# HV_amplifier.net
KiCad netlist of a schematic drawn in Altium Designer
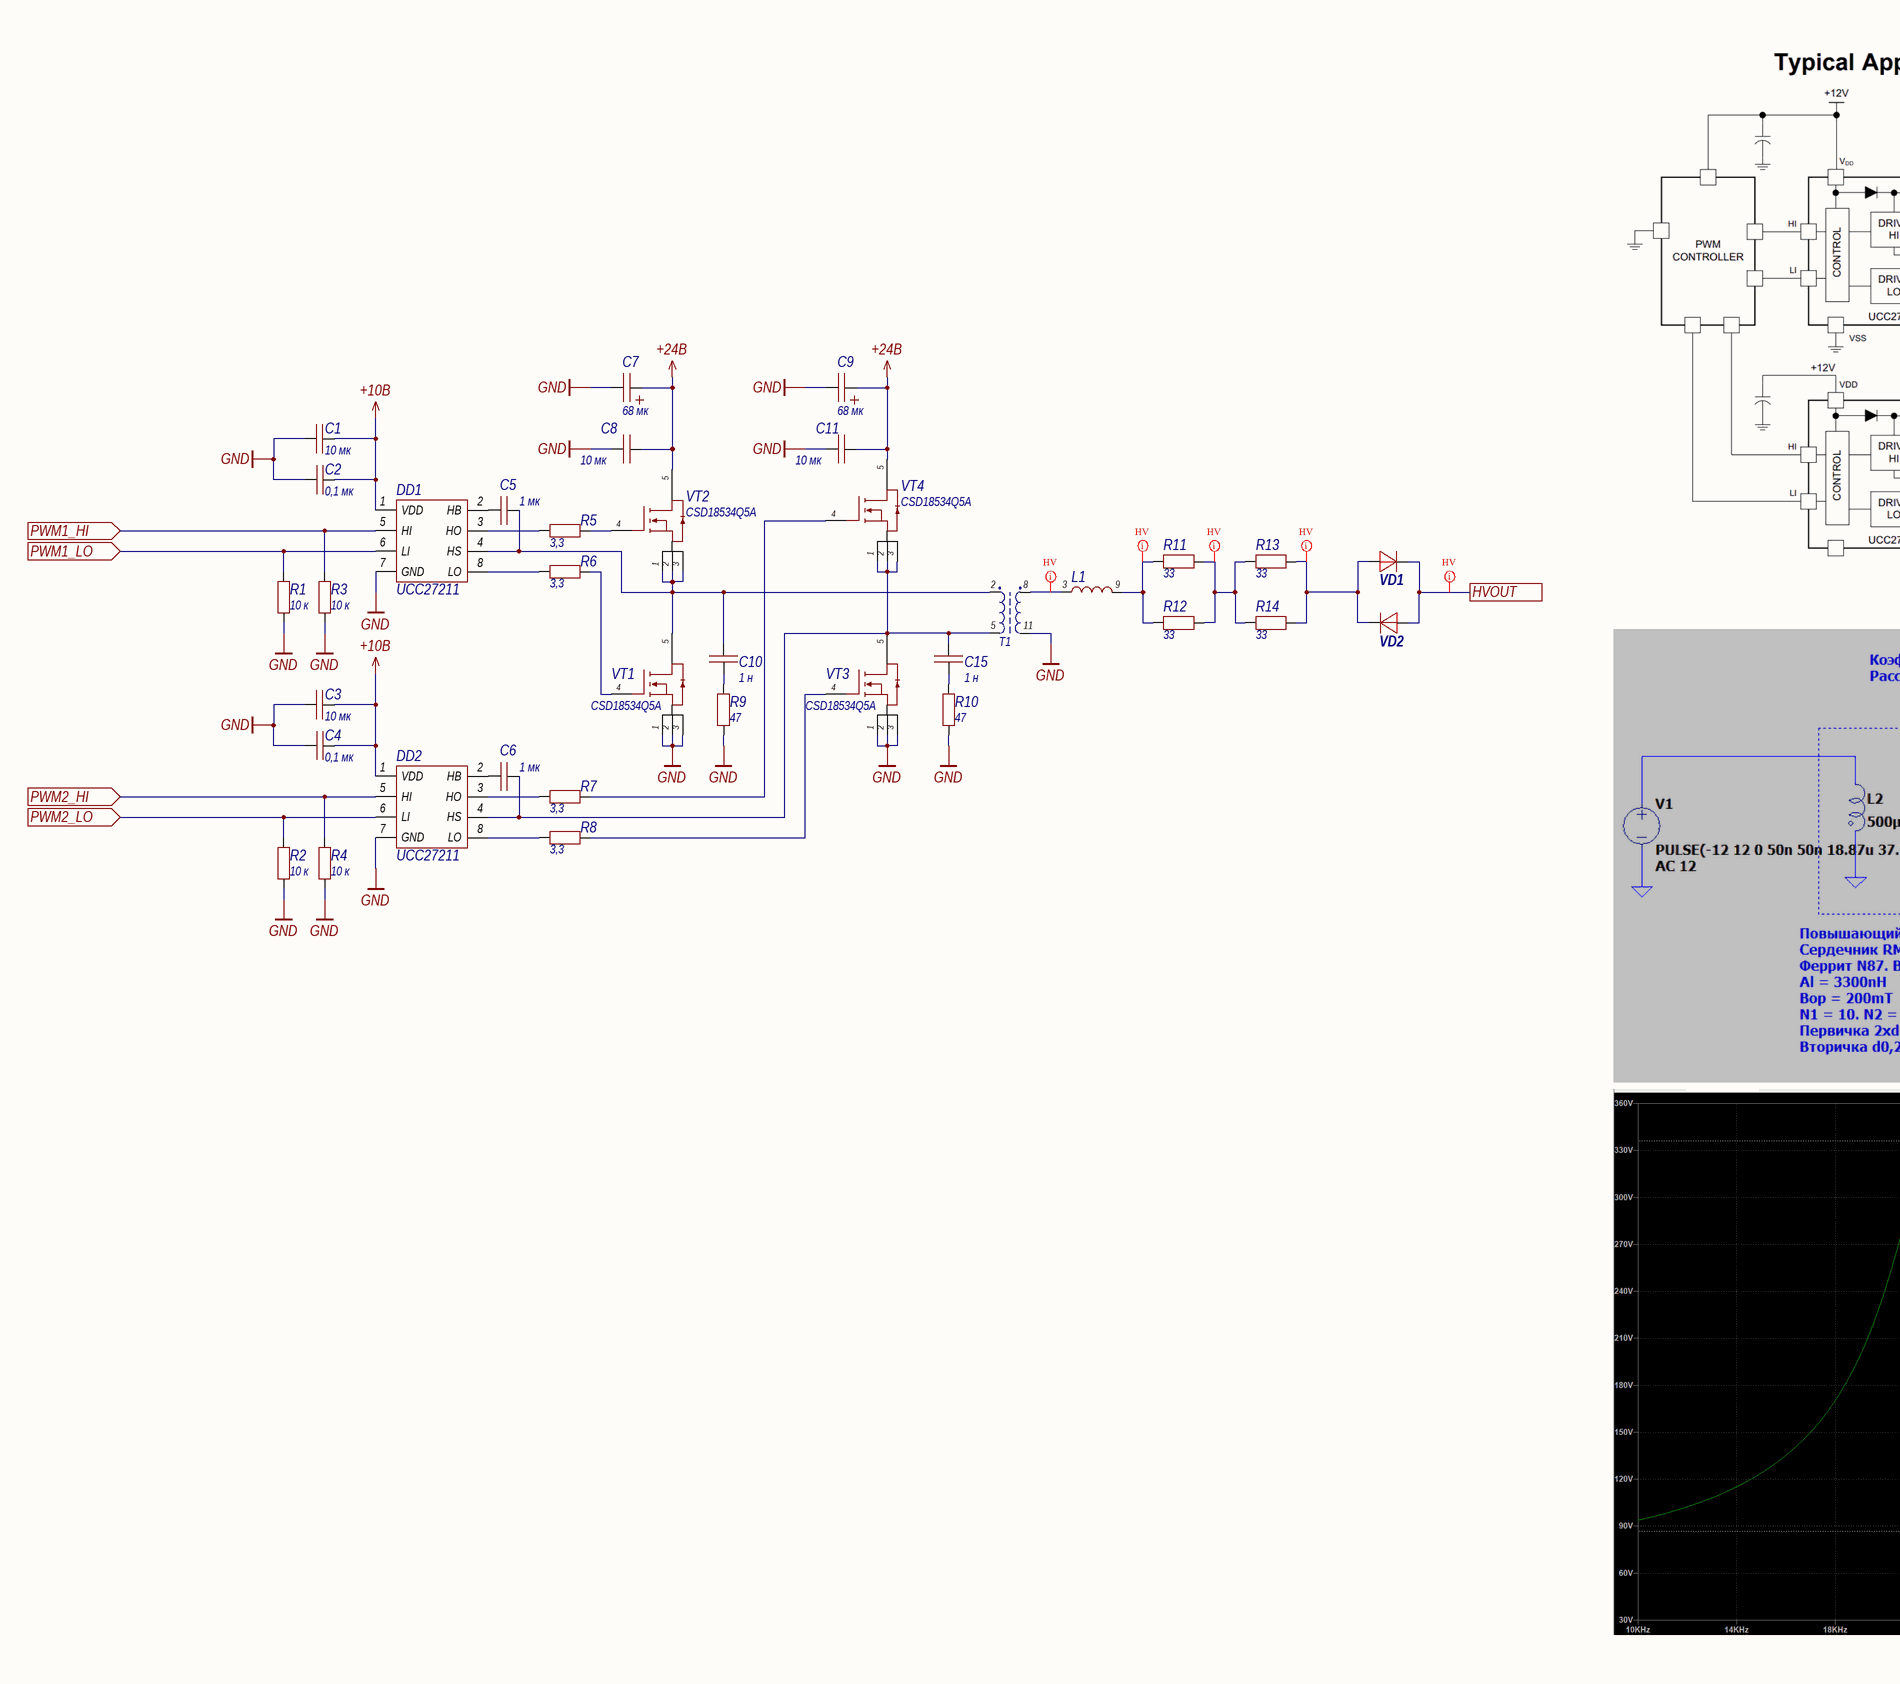
[diagram p0: HV_amplifier.SchDoc, left]
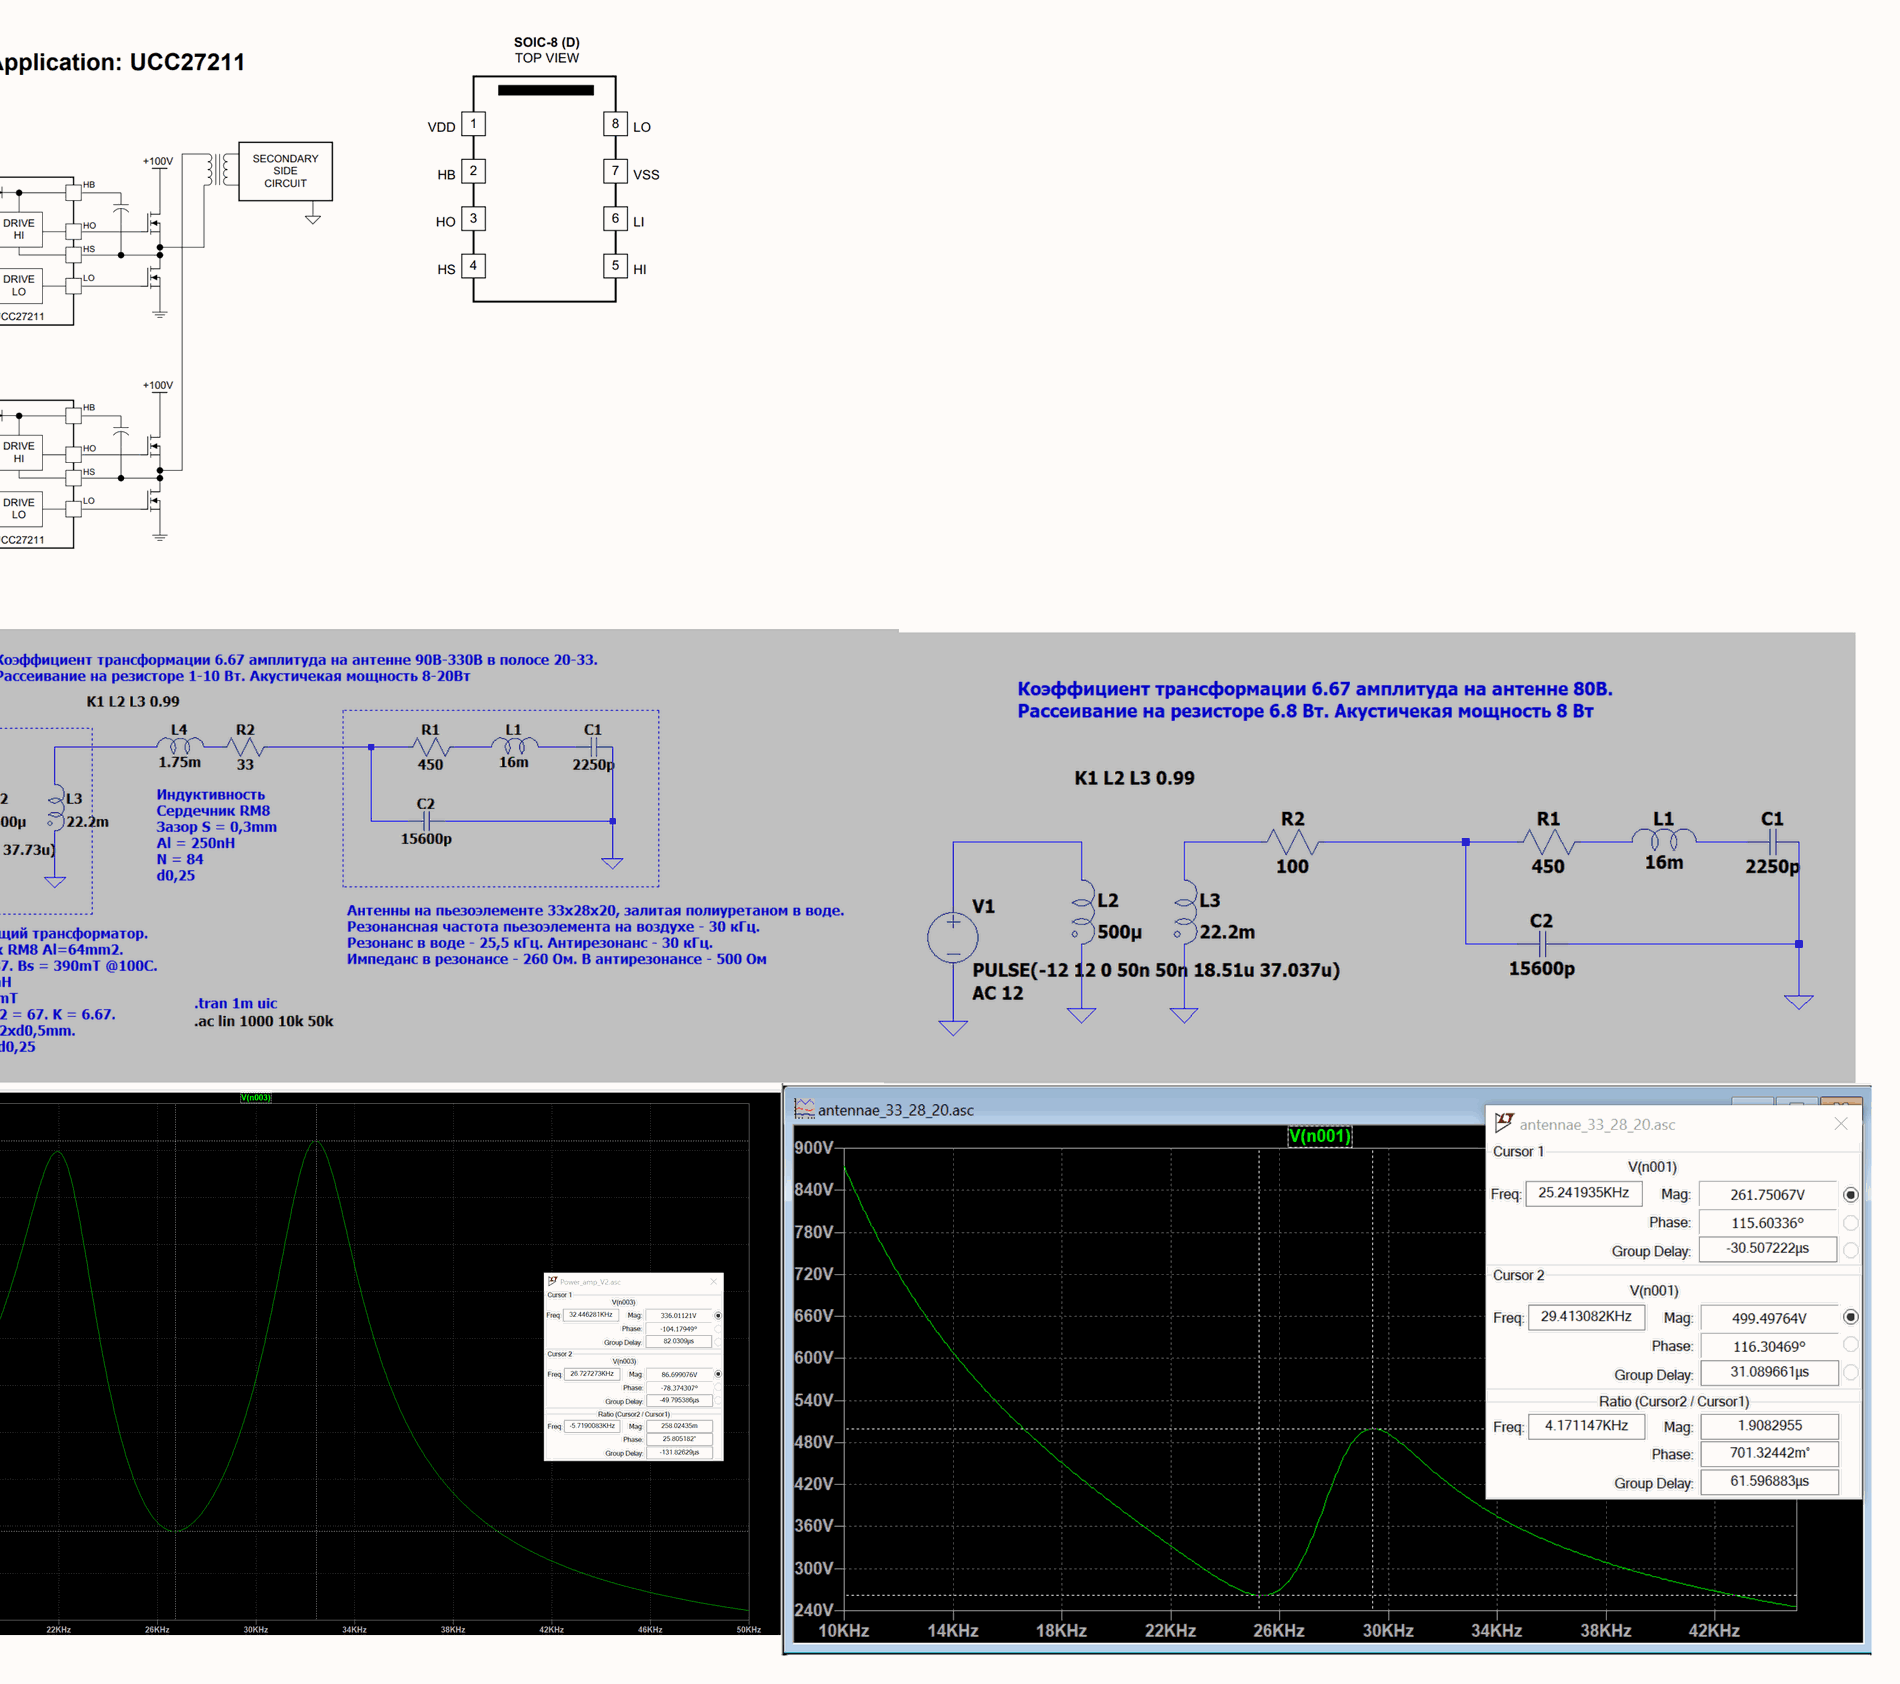
[diagram p1: HV_amplifier.SchDoc, right]

(export (version "E")
  (design (tool "Eeschema 10.0.6"))
  (components
    (comp (ref "C1")
      (value "10 мк")
      (footprint "1210C")
      (description "Конденсатор 1210C ёмкостью 10 мк 10%, 35 В, X7R")
      (fields (field (name "PART NUMBER") "Capacitor_10u_10_35V_X7R_1210C") (field (name "TOLERANCE") "10%"))
      (libsource (lib "Hydrolib") (part "Capacitor"))
    )
    (comp (ref "C2")
      (value "0,1 мк")
      (footprint "0603C")
      (description "Конденсатор 0603C ёмкостью 0,1 мк 10%, 50 В, X7R")
      (fields (field (name "PART NUMBER") "Capacitor_0,1u_10_50V_X7R_0603C") (field (name "TOLERANCE") "10%"))
      (libsource (lib "Hydrolib") (part "Capacitor"))
    )
    (comp (ref "C3")
      (value "10 мк")
      (footprint "1210C")
      (description "Конденсатор 1210C ёмкостью 10 мк 10%, 35 В, X7R")
      (fields (field (name "PART NUMBER") "Capacitor_10u_10_35V_X7R_1210C") (field (name "TOLERANCE") "10%"))
      (libsource (lib "Hydrolib") (part "Capacitor"))
    )
    (comp (ref "C4")
      (value "0,1 мк")
      (footprint "0603C")
      (description "Конденсатор 0603C ёмкостью 0,1 мк 10%, 50 В, X7R")
      (fields (field (name "PART NUMBER") "Capacitor_0,1u_10_50V_X7R_0603C") (field (name "TOLERANCE") "10%"))
      (libsource (lib "Hydrolib") (part "Capacitor"))
    )
    (comp (ref "C5")
      (value "1 мк")
      (footprint "0603C")
      (description "Конденсатор 0603C ёмкостью 1 мк 10%, 25 В, X7R")
      (fields (field (name "PART NUMBER") "Capacitor_1u_10_25V_X7R_0603C") (field (name "TOLERANCE") "10%"))
      (libsource (lib "Hydrolib") (part "Capacitor"))
    )
    (comp (ref "C6")
      (value "1 мк")
      (footprint "0603C")
      (description "Конденсатор 0603C ёмкостью 1 мк 10%, 25 В, X7R")
      (fields (field (name "PART NUMBER") "Capacitor_1u_10_25V_X7R_0603C") (field (name "TOLERANCE") "10%"))
      (libsource (lib "Hydrolib") (part "Capacitor"))
    )
    (comp (ref "C7")
      (value "68 мк")
      (footprint "CAP_SMD_10x12,7")
      (fields
        (field (name "PART NUMBER") "50SVPF68M")
        (field (name "TOLERANCE") "20")
        (field (name "Comment") "Capacitor")
        (field (name "АВТОР") "glebmih")
      )
      (libsource (lib "Hydrolib") (part "Capacitor_polar"))
    )
    (comp (ref "C8")
      (value "10 мк")
      (footprint "1210C")
      (description "Конденсатор 1210C ёмкостью 10 мк 10%, 35 В, X7R")
      (fields (field (name "PART NUMBER") "Capacitor_10u_10_35V_X7R_1210C") (field (name "TOLERANCE") "10%"))
      (libsource (lib "Hydrolib") (part "Capacitor"))
    )
    (comp (ref "C9")
      (value "68 мк")
      (footprint "CAP_SMD_10x12,7")
      (fields
        (field (name "PART NUMBER") "50SVPF68M")
        (field (name "TOLERANCE") "20")
        (field (name "Comment") "Capacitor")
        (field (name "АВТОР") "glebmih")
      )
      (libsource (lib "Hydrolib") (part "Capacitor_polar"))
    )
    (comp (ref "C10")
      (value "1 н")
      (footprint "0603C")
      (description "Конденсатор 0603C ёмкостью 1 н 5%, 50 В, NP0")
      (fields
        (field (name "PART NUMBER") "Capacitor_1n_5_50V_NP0_0603C")
        (field (name "TOLERANCE") "5%")
        (field (name "АВТОР") "glebmih")
      )
      (libsource (lib "Hydrolib") (part "Capacitor"))
    )
    (comp (ref "C11")
      (value "10 мк")
      (footprint "1210C")
      (description "Конденсатор 1210C ёмкостью 10 мк 10%, 35 В, X7R")
      (fields (field (name "PART NUMBER") "Capacitor_10u_10_35V_X7R_1210C") (field (name "TOLERANCE") "10%"))
      (libsource (lib "Hydrolib") (part "Capacitor"))
    )
    (comp (ref "C15")
      (value "1 н")
      (footprint "0603C")
      (description "Конденсатор 0603C ёмкостью 1 н 5%, 50 В, NP0")
      (fields
        (field (name "PART NUMBER") "Capacitor_1n_5_50V_NP0_0603C")
        (field (name "TOLERANCE") "5%")
        (field (name "АВТОР") "glebmih")
      )
      (libsource (lib "Hydrolib") (part "Capacitor"))
    )
    (comp (ref "DD1")
      (value "UCC27211")
      (footprint "SOIC-8")
      (description "Полумостовой драйвер затвора для mosfet транзисторов")
      (fields (field (name "АВТОР") "glebmih"))
      (libsource (lib "Hydrolib") (part "UCC27211"))
    )
    (comp (ref "DD2")
      (value "UCC27211")
      (footprint "SOIC-8")
      (description "Полумостовой драйвер затвора для mosfet транзисторов")
      (fields (field (name "АВТОР") "glebmih"))
      (libsource (lib "Hydrolib") (part "UCC27211"))
    )
    (comp (ref "L1")
      (value "Inductance_RM8")
      (footprint "RM8_trans")
      (description "Индуктивность на сердечнике RM8")
      (fields (field (name "АВТОР") "glebmih"))
      (libsource (lib "Hydrolib") (part "Inductance_RM8"))
    )
    (comp (ref "R1")
      (value "10 к")
      (footprint "0603R")
      (description "Резистор номиналом 10 кОм 1%")
      (fields (field (name "PART NUMBER") "Resistor_10k_1_0603") (field (name "TOLERANCE") "1%"))
      (libsource (lib "") (part "Resistor_1"))
    )
    (comp (ref "R2")
      (value "10 к")
      (footprint "0603R")
      (description "Резистор номиналом 10 кОм 1%")
      (fields (field (name "PART NUMBER") "Resistor_10k_1_0603") (field (name "TOLERANCE") "1%"))
      (libsource (lib "") (part "Resistor_1"))
    )
    (comp (ref "R3")
      (value "10 к")
      (footprint "0603R")
      (description "Резистор номиналом 10 кОм 1%")
      (fields (field (name "PART NUMBER") "Resistor_10k_1_0603") (field (name "TOLERANCE") "1%"))
      (libsource (lib "") (part "Resistor_1"))
    )
    (comp (ref "R4")
      (value "10 к")
      (footprint "0603R")
      (description "Резистор номиналом 10 кОм 1%")
      (fields (field (name "PART NUMBER") "Resistor_10k_1_0603") (field (name "TOLERANCE") "1%"))
      (libsource (lib "") (part "Resistor_1"))
    )
    (comp (ref "R5")
      (value "3,3")
      (footprint "0603R")
      (description "Резистор номиналом 3,3 Ом 1%")
      (fields (field (name "PART NUMBER") "Resistor_3.3_1_0603") (field (name "TOLERANCE") "1%"))
      (libsource (lib "Hydrolib") (part "Resistor"))
    )
    (comp (ref "R6")
      (value "3,3")
      (footprint "0603R")
      (description "Резистор номиналом 3,3 Ом 1%")
      (fields (field (name "PART NUMBER") "Resistor_3.3_1_0603") (field (name "TOLERANCE") "1%"))
      (libsource (lib "Hydrolib") (part "Resistor"))
    )
    (comp (ref "R7")
      (value "3,3")
      (footprint "0603R")
      (description "Резистор номиналом 3,3 Ом 1%")
      (fields (field (name "PART NUMBER") "Resistor_3.3_1_0603") (field (name "TOLERANCE") "1%"))
      (libsource (lib "Hydrolib") (part "Resistor"))
    )
    (comp (ref "R8")
      (value "3,3")
      (footprint "0603R")
      (description "Резистор номиналом 3,3 Ом 1%")
      (fields (field (name "PART NUMBER") "Resistor_3.3_1_0603") (field (name "TOLERANCE") "1%"))
      (libsource (lib "Hydrolib") (part "Resistor"))
    )
    (comp (ref "R9")
      (value "47")
      (footprint "0805R")
      (description "Резистор номиналом 47 Ом 1%")
      (fields
        (field (name "PART NUMBER") "Resistor_47_1_0805")
        (field (name "TOLERANCE") "1%")
        (field (name "АВТОР") "glebmih")
      )
      (libsource (lib "") (part "Resistor_1"))
    )
    (comp (ref "R10")
      (value "47")
      (footprint "0805R")
      (description "Резистор номиналом 47 Ом 1%")
      (fields
        (field (name "PART NUMBER") "Resistor_47_1_0805")
        (field (name "TOLERANCE") "1%")
        (field (name "АВТОР") "glebmih")
      )
      (libsource (lib "") (part "Resistor_1"))
    )
    (comp (ref "R11")
      (value "33")
      (footprint "2512R")
      (description "Резистор номиналом 33 Ом 1%")
      (fields
        (field (name "PART NUMBER") "Resistor_33_1_2512")
        (field (name "TOLERANCE") "1%")
        (field (name "АВТОР") "glebmih")
      )
      (libsource (lib "Hydrolib") (part "Resistor"))
    )
    (comp (ref "R12")
      (value "33")
      (footprint "2512R")
      (description "Резистор номиналом 33 Ом 1%")
      (fields
        (field (name "PART NUMBER") "Resistor_33_1_2512")
        (field (name "TOLERANCE") "1%")
        (field (name "АВТОР") "glebmih")
      )
      (libsource (lib "Hydrolib") (part "Resistor"))
    )
    (comp (ref "R13")
      (value "33")
      (footprint "2512R")
      (description "Резистор номиналом 33 Ом 1%")
      (fields
        (field (name "PART NUMBER") "Resistor_33_1_2512")
        (field (name "TOLERANCE") "1%")
        (field (name "АВТОР") "glebmih")
      )
      (libsource (lib "Hydrolib") (part "Resistor"))
    )
    (comp (ref "R14")
      (value "33")
      (footprint "2512R")
      (description "Резистор номиналом 33 Ом 1%")
      (fields
        (field (name "PART NUMBER") "Resistor_33_1_2512")
        (field (name "TOLERANCE") "1%")
        (field (name "АВТОР") "glebmih")
      )
      (libsource (lib "Hydrolib") (part "Resistor"))
    )
    (comp (ref "T1")
      (value "Transformer_RM8")
      (footprint "RM8_trans")
      (description "Трансформатор на сердечнике RM8")
      (fields (field (name "АВТОР") "glebmih"))
      (libsource (lib "Hydrolib") (part "Transformer_RM8"))
    )
    (comp (ref "VD1")
      (value "SMA4007")
      (footprint "SMA")
      (description "Выпрямительный диод на 1000 В, ном. ток 1 А А")
      (fields (field (name "АВТОР") "glebmih"))
      (libsource (lib "Hydrolib") (part "Rectifier_diode"))
    )
    (comp (ref "VD2")
      (value "SMA4007")
      (footprint "SMA")
      (description "Выпрямительный диод на 1000 В, ном. ток 1 А А")
      (fields (field (name "АВТОР") "glebmih"))
      (libsource (lib "Hydrolib") (part "Rectifier_diode"))
    )
    (comp (ref "VT1")
      (value "CSD18534Q5A")
      (footprint "SON-8_5x6")
      (description "N-канальный MOSFET, 60 В, 50 А")
      (fields (field (name "АВТОР") "glebmih"))
      (libsource (lib "Hydrolib") (part "MOSFET_N-channel_5pin"))
    )
    (comp (ref "VT2")
      (value "CSD18534Q5A")
      (footprint "SON-8_5x6")
      (description "N-канальный MOSFET, 60 В, 50 А")
      (fields (field (name "АВТОР") "glebmih"))
      (libsource (lib "Hydrolib") (part "MOSFET_N-channel_5pin"))
    )
    (comp (ref "VT3")
      (value "CSD18534Q5A")
      (footprint "SON-8_5x6")
      (description "N-канальный MOSFET, 60 В, 50 А")
      (fields (field (name "АВТОР") "glebmih"))
      (libsource (lib "Hydrolib") (part "MOSFET_N-channel_5pin"))
    )
    (comp (ref "VT4")
      (value "CSD18534Q5A")
      (footprint "SON-8_5x6")
      (description "N-канальный MOSFET, 60 В, 50 А")
      (fields (field (name "АВТОР") "glebmih"))
      (libsource (lib "Hydrolib") (part "MOSFET_N-channel_5pin"))
    )
  )
  (nets
    (net (code "1") (name "+10В") (class "Default")
      (node (ref "C1") (pin "1") (pinfunction "1_1") (pintype "passive"))
      (node (ref "C2") (pin "2") (pinfunction "2_2") (pintype "passive"))
      (node (ref "C3") (pin "1") (pinfunction "1_1") (pintype "passive"))
      (node (ref "C4") (pin "2") (pinfunction "2_2") (pintype "passive"))
      (node (ref "DD1") (pin "1") (pinfunction "VDD_1") (pintype "passive"))
      (node (ref "DD2") (pin "1") (pinfunction "VDD_1") (pintype "passive"))
    )
    (net (code "2") (name "+24В") (class "Default")
      (node (ref "C11") (pin "2") (pinfunction "2_2") (pintype "passive"))
      (node (ref "C7") (pin "1") (pinfunction "1_1") (pintype "passive"))
      (node (ref "C8") (pin "2") (pinfunction "2_2") (pintype "passive"))
      (node (ref "C9") (pin "1") (pinfunction "1_1") (pintype "passive"))
      (node (ref "VT2") (pin "5") (pinfunction "5_5") (pintype "passive"))
      (node (ref "VT4") (pin "5") (pinfunction "5_5") (pintype "passive"))
    )
    (net (code "3") (name "/HVOUT") (class "Default")
      (node (ref "VD1") (pin "2") (pinfunction "2_2") (pintype "passive"))
      (node (ref "VD2") (pin "1") (pinfunction "1_1") (pintype "passive"))
    )
    (net (code "4") (name "/PWM1_HI") (class "Default")
      (node (ref "DD1") (pin "5") (pinfunction "HI_5") (pintype "passive"))
      (node (ref "R3") (pin "2") (pinfunction "2_2") (pintype "passive"))
    )
    (net (code "5") (name "/PWM1_LO") (class "Default")
      (node (ref "DD1") (pin "6") (pinfunction "LI_6") (pintype "passive"))
      (node (ref "R1") (pin "2") (pinfunction "2_2") (pintype "passive"))
    )
    (net (code "6") (name "/PWM2_HI") (class "Default")
      (node (ref "DD2") (pin "5") (pinfunction "HI_5") (pintype "passive"))
      (node (ref "R4") (pin "2") (pinfunction "2_2") (pintype "passive"))
    )
    (net (code "7") (name "/PWM2_LO") (class "Default")
      (node (ref "DD2") (pin "6") (pinfunction "LI_6") (pintype "passive"))
      (node (ref "R2") (pin "2") (pinfunction "2_2") (pintype "passive"))
    )
    (net (code "8") (name "GND") (class "Default")
      (node (ref "C1") (pin "2") (pinfunction "2_2") (pintype "passive"))
      (node (ref "C11") (pin "1") (pinfunction "1_1") (pintype "passive"))
      (node (ref "C2") (pin "1") (pinfunction "1_1") (pintype "passive"))
      (node (ref "C3") (pin "2") (pinfunction "2_2") (pintype "passive"))
      (node (ref "C4") (pin "1") (pinfunction "1_1") (pintype "passive"))
      (node (ref "C7") (pin "2") (pinfunction "2_2") (pintype "passive"))
      (node (ref "C8") (pin "1") (pinfunction "1_1") (pintype "passive"))
      (node (ref "C9") (pin "2") (pinfunction "2_2") (pintype "passive"))
      (node (ref "DD1") (pin "7") (pinfunction "GND_7") (pintype "passive"))
      (node (ref "DD2") (pin "7") (pinfunction "GND_7") (pintype "passive"))
      (node (ref "R1") (pin "1") (pinfunction "1_1") (pintype "passive"))
      (node (ref "R10") (pin "1") (pinfunction "1_1") (pintype "passive"))
      (node (ref "R2") (pin "1") (pinfunction "1_1") (pintype "passive"))
      (node (ref "R3") (pin "1") (pinfunction "1_1") (pintype "passive"))
      (node (ref "R4") (pin "1") (pinfunction "1_1") (pintype "passive"))
      (node (ref "R9") (pin "1") (pinfunction "1_1") (pintype "passive"))
      (node (ref "T1") (pin "11") (pinfunction "4_11") (pintype "passive"))
      (node (ref "VT1") (pin "1") (pinfunction "1_1") (pintype "passive"))
      (node (ref "VT1") (pin "2") (pinfunction "2_2") (pintype "passive"))
      (node (ref "VT1") (pin "3") (pinfunction "3_3") (pintype "passive"))
      (node (ref "VT3") (pin "1") (pinfunction "1_1") (pintype "passive"))
      (node (ref "VT3") (pin "2") (pinfunction "2_2") (pintype "passive"))
      (node (ref "VT3") (pin "3") (pinfunction "3_3") (pintype "passive"))
    )
    (net (code "9") (name "Net-(C10-Pad1)") (class "Default")
      (node (ref "C10") (pin "1") (pinfunction "1_1") (pintype "passive"))
      (node (ref "R9") (pin "2") (pinfunction "2_2") (pintype "passive"))
    )
    (net (code "10") (name "Net-(C15-Pad1)") (class "Default")
      (node (ref "C15") (pin "1") (pinfunction "1_1") (pintype "passive"))
      (node (ref "R10") (pin "2") (pinfunction "2_2") (pintype "passive"))
    )
    (net (code "11") (name "Net-(DD1-HB)") (class "Default")
      (node (ref "C5") (pin "1") (pinfunction "1_1") (pintype "passive"))
      (node (ref "DD1") (pin "2") (pinfunction "HB_2") (pintype "passive"))
    )
    (net (code "12") (name "Net-(DD1-HO)") (class "Default")
      (node (ref "DD1") (pin "3") (pinfunction "HO_3") (pintype "passive"))
      (node (ref "R5") (pin "1") (pinfunction "1_1") (pintype "passive"))
    )
    (net (code "13") (name "Net-(DD1-HS)") (class "Default")
      (node (ref "C10") (pin "2") (pinfunction "2_2") (pintype "passive"))
      (node (ref "C5") (pin "2") (pinfunction "2_2") (pintype "passive"))
      (node (ref "DD1") (pin "4") (pinfunction "HS_4") (pintype "passive"))
      (node (ref "T1") (pin "2") (pinfunction "2_2") (pintype "passive"))
      (node (ref "VT1") (pin "5") (pinfunction "5_5") (pintype "passive"))
      (node (ref "VT2") (pin "1") (pinfunction "1_1") (pintype "passive"))
      (node (ref "VT2") (pin "2") (pinfunction "2_2") (pintype "passive"))
      (node (ref "VT2") (pin "3") (pinfunction "3_3") (pintype "passive"))
    )
    (net (code "14") (name "Net-(DD1-LO)") (class "Default")
      (node (ref "DD1") (pin "8") (pinfunction "LO_8") (pintype "passive"))
      (node (ref "R6") (pin "1") (pinfunction "1_1") (pintype "passive"))
    )
    (net (code "15") (name "Net-(DD2-HB)") (class "Default")
      (node (ref "C6") (pin "1") (pinfunction "1_1") (pintype "passive"))
      (node (ref "DD2") (pin "2") (pinfunction "HB_2") (pintype "passive"))
    )
    (net (code "16") (name "Net-(DD2-HO)") (class "Default")
      (node (ref "DD2") (pin "3") (pinfunction "HO_3") (pintype "passive"))
      (node (ref "R7") (pin "1") (pinfunction "1_1") (pintype "passive"))
    )
    (net (code "17") (name "Net-(DD2-HS)") (class "Default")
      (node (ref "C15") (pin "2") (pinfunction "2_2") (pintype "passive"))
      (node (ref "C6") (pin "2") (pinfunction "2_2") (pintype "passive"))
      (node (ref "DD2") (pin "4") (pinfunction "HS_4") (pintype "passive"))
      (node (ref "T1") (pin "5") (pinfunction "5_5") (pintype "passive"))
      (node (ref "VT3") (pin "5") (pinfunction "5_5") (pintype "passive"))
      (node (ref "VT4") (pin "1") (pinfunction "1_1") (pintype "passive"))
      (node (ref "VT4") (pin "2") (pinfunction "2_2") (pintype "passive"))
      (node (ref "VT4") (pin "3") (pinfunction "3_3") (pintype "passive"))
    )
    (net (code "18") (name "Net-(DD2-LO)") (class "Default")
      (node (ref "DD2") (pin "8") (pinfunction "LO_8") (pintype "passive"))
      (node (ref "R8") (pin "1") (pinfunction "1_1") (pintype "passive"))
    )
    (net (code "19") (name "Net-(L1-Pad9)") (class "Default")
      (node (ref "L1") (pin "9") (pinfunction "9_9") (pintype "passive"))
      (node (ref "R11") (pin "1") (pinfunction "1_1") (pintype "passive"))
      (node (ref "R12") (pin "1") (pinfunction "1_1") (pintype "passive"))
    )
    (net (code "20") (name "Net-(R5-Pad2)") (class "Default")
      (node (ref "R5") (pin "2") (pinfunction "2_2") (pintype "passive"))
      (node (ref "VT2") (pin "4") (pinfunction "4_4") (pintype "passive"))
    )
    (net (code "21") (name "Net-(R6-Pad2)") (class "Default")
      (node (ref "R6") (pin "2") (pinfunction "2_2") (pintype "passive"))
      (node (ref "VT1") (pin "4") (pinfunction "4_4") (pintype "passive"))
    )
    (net (code "22") (name "Net-(R7-Pad2)") (class "Default")
      (node (ref "R7") (pin "2") (pinfunction "2_2") (pintype "passive"))
      (node (ref "VT4") (pin "4") (pinfunction "4_4") (pintype "passive"))
    )
    (net (code "23") (name "Net-(R8-Pad2)") (class "Default")
      (node (ref "R8") (pin "2") (pinfunction "2_2") (pintype "passive"))
      (node (ref "VT3") (pin "4") (pinfunction "4_4") (pintype "passive"))
    )
    (net (code "24") (name "Net-(R11-Pad2)") (class "Default")
      (node (ref "R11") (pin "2") (pinfunction "2_2") (pintype "passive"))
      (node (ref "R12") (pin "2") (pinfunction "2_2") (pintype "passive"))
      (node (ref "R13") (pin "1") (pinfunction "1_1") (pintype "passive"))
      (node (ref "R14") (pin "1") (pinfunction "1_1") (pintype "passive"))
    )
    (net (code "25") (name "Net-(R13-Pad2)") (class "Default")
      (node (ref "R13") (pin "2") (pinfunction "2_2") (pintype "passive"))
      (node (ref "R14") (pin "2") (pinfunction "2_2") (pintype "passive"))
      (node (ref "VD1") (pin "1") (pinfunction "1_1") (pintype "passive"))
      (node (ref "VD2") (pin "2") (pinfunction "2_2") (pintype "passive"))
    )
    (net (code "26") (name "Net-(T1-3)") (class "Default")
      (node (ref "L1") (pin "3") (pinfunction "3_3") (pintype "passive"))
      (node (ref "T1") (pin "8") (pinfunction "3_8") (pintype "passive"))
    )
  )
)
